# sternkoppler_4fach.net
KiCad netlist of a schematic drawn in EAGLE
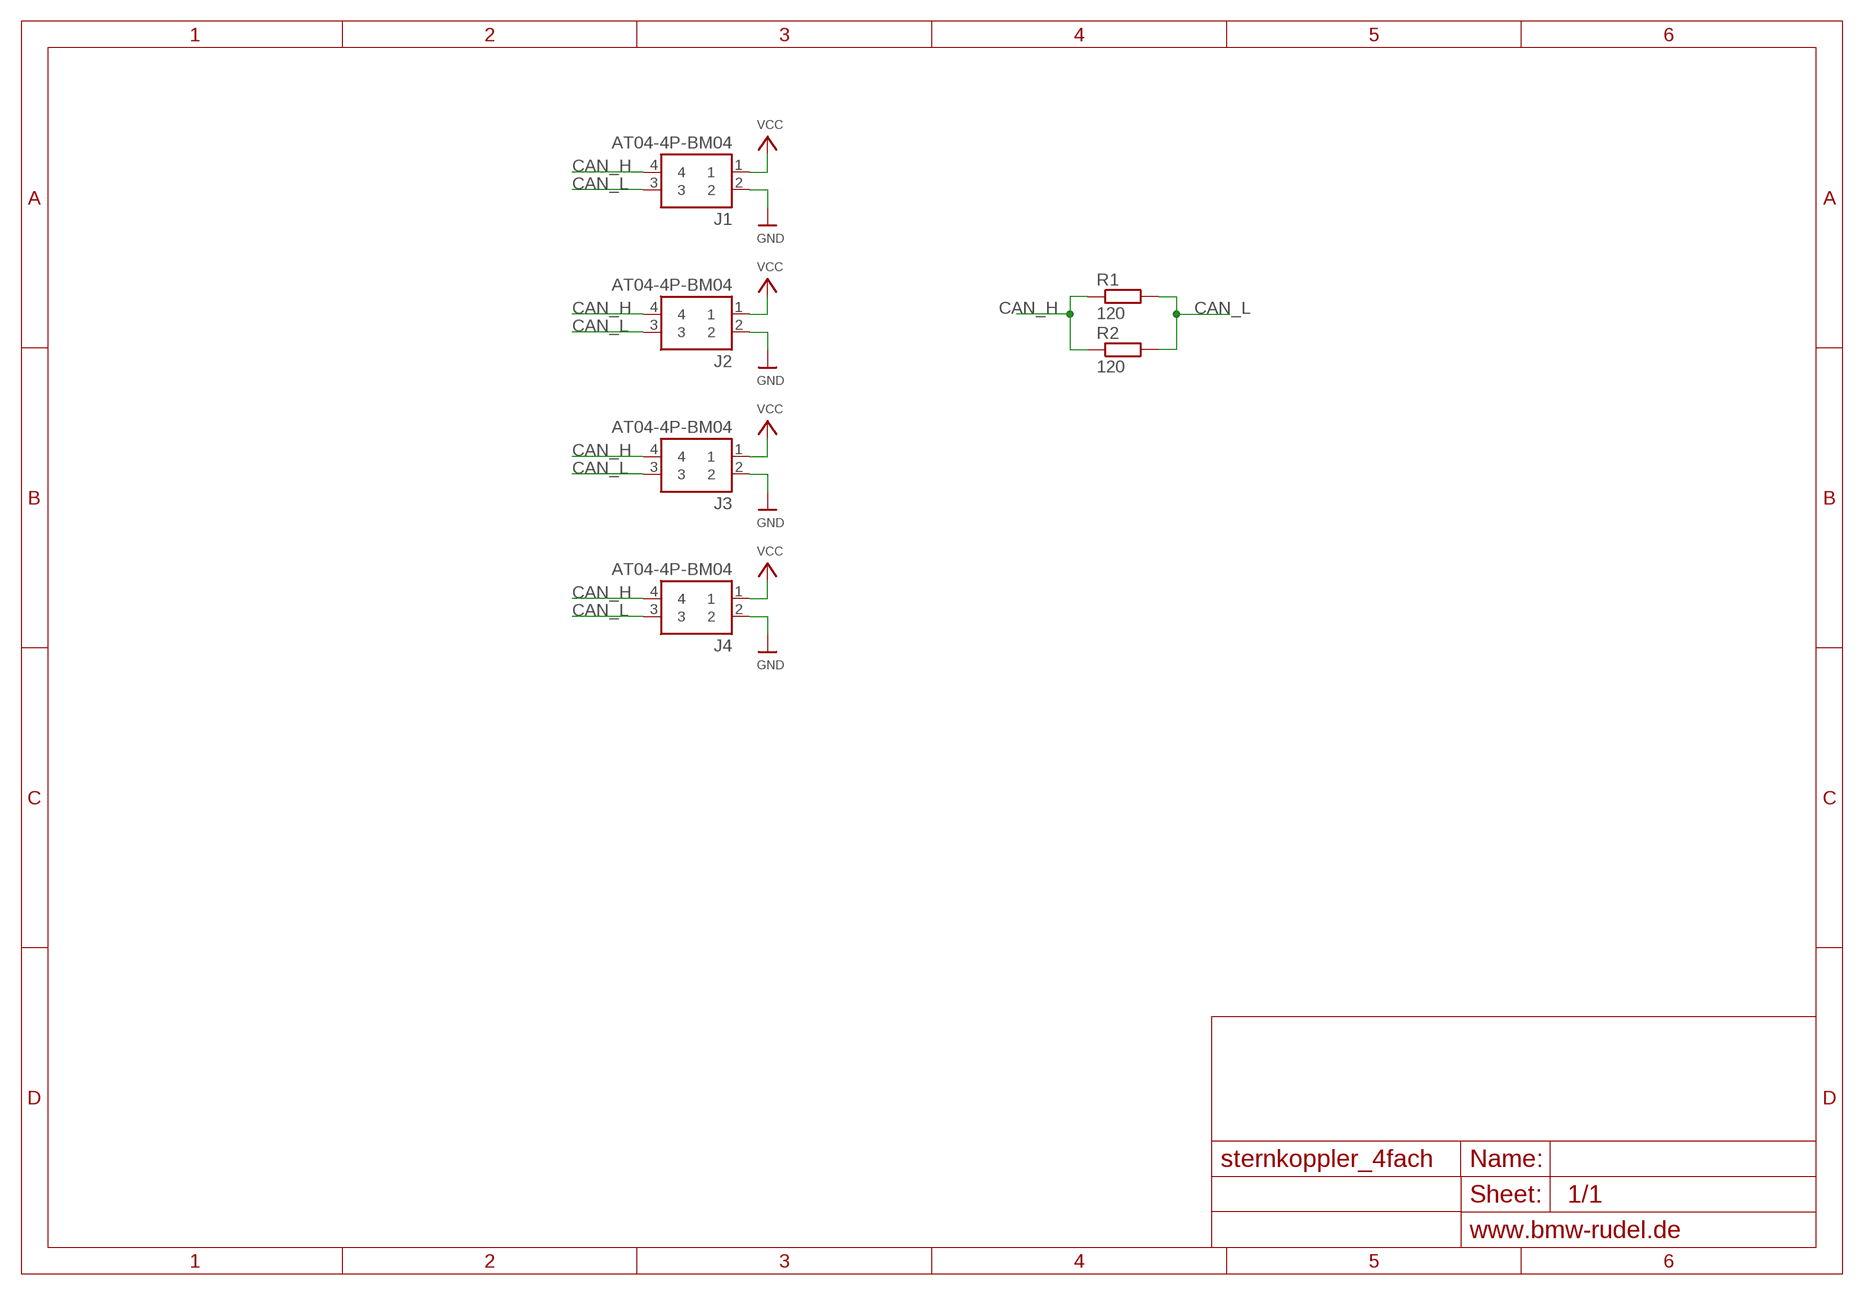
[diagram p0: schematic, sheet 1]

(export (version "E")
  (design (tool "Eeschema 10.0.6"))
  (components
    (comp (ref "J1")
      (value "AT04-4P-BM04")
      (footprint "eagle-import:AT044PBM04")
      (fields (field (name "MOUSER_PART_NUMBER") "654-AT04-4P-BM04"))
      (libsource (lib "eagle-import") (part "AT04-4P-BM04"))
    )
    (comp (ref "J2")
      (value "AT04-4P-BM04")
      (footprint "eagle-import:AT044PBM04")
      (fields (field (name "MOUSER_PART_NUMBER") "654-AT04-4P-BM04"))
      (libsource (lib "eagle-import") (part "AT04-4P-BM04"))
    )
    (comp (ref "J3")
      (value "AT04-4P-BM04")
      (footprint "eagle-import:AT044PBM04")
      (fields (field (name "MOUSER_PART_NUMBER") "654-AT04-4P-BM04"))
      (libsource (lib "eagle-import") (part "AT04-4P-BM04"))
    )
    (comp (ref "J4")
      (value "AT04-4P-BM04")
      (footprint "eagle-import:AT044PBM04")
      (fields (field (name "MOUSER_PART_NUMBER") "654-AT04-4P-BM04"))
      (libsource (lib "eagle-import") (part "AT04-4P-BM04"))
    )
    (comp (ref "R1")
      (value "120")
      (footprint "eagle-import:R0805")
      (libsource (lib "eagle-import") (part "R-EU_R0805"))
    )
    (comp (ref "R2")
      (value "120")
      (footprint "eagle-import:R0805")
      (libsource (lib "eagle-import") (part "R-EU_R0805"))
    )
  )
  (nets
    (net (code "1") (name "/CAN_H") (class "Default")
      (node (ref "J1") (pin "4") (pinfunction "4_4") (pintype "bidirectional"))
      (node (ref "J2") (pin "4") (pinfunction "4_4") (pintype "bidirectional"))
      (node (ref "J3") (pin "4") (pinfunction "4_4") (pintype "bidirectional"))
      (node (ref "J4") (pin "4") (pinfunction "4_4") (pintype "bidirectional"))
      (node (ref "R1") (pin "1") (pinfunction "1_1") (pintype "passive"))
      (node (ref "R2") (pin "1") (pinfunction "1_1") (pintype "passive"))
    )
    (net (code "2") (name "/CAN_L") (class "Default")
      (node (ref "J1") (pin "3") (pinfunction "3_3") (pintype "bidirectional"))
      (node (ref "J2") (pin "3") (pinfunction "3_3") (pintype "bidirectional"))
      (node (ref "J3") (pin "3") (pinfunction "3_3") (pintype "bidirectional"))
      (node (ref "J4") (pin "3") (pinfunction "3_3") (pintype "bidirectional"))
      (node (ref "R1") (pin "2") (pinfunction "2_2") (pintype "passive"))
      (node (ref "R2") (pin "2") (pinfunction "2_2") (pintype "passive"))
    )
    (net (code "3") (name "GND") (class "Default")
      (node (ref "J1") (pin "2") (pinfunction "2_2") (pintype "bidirectional"))
      (node (ref "J2") (pin "2") (pinfunction "2_2") (pintype "bidirectional"))
      (node (ref "J3") (pin "2") (pinfunction "2_2") (pintype "bidirectional"))
      (node (ref "J4") (pin "2") (pinfunction "2_2") (pintype "bidirectional"))
    )
    (net (code "4") (name "VCC") (class "Default")
      (node (ref "J1") (pin "1") (pinfunction "1_1") (pintype "bidirectional"))
      (node (ref "J2") (pin "1") (pinfunction "1_1") (pintype "bidirectional"))
      (node (ref "J3") (pin "1") (pinfunction "1_1") (pintype "bidirectional"))
      (node (ref "J4") (pin "1") (pinfunction "1_1") (pintype "bidirectional"))
    )
  )
)
